# 1.net
KiCad netlist of a schematic drawn in Altium Designer
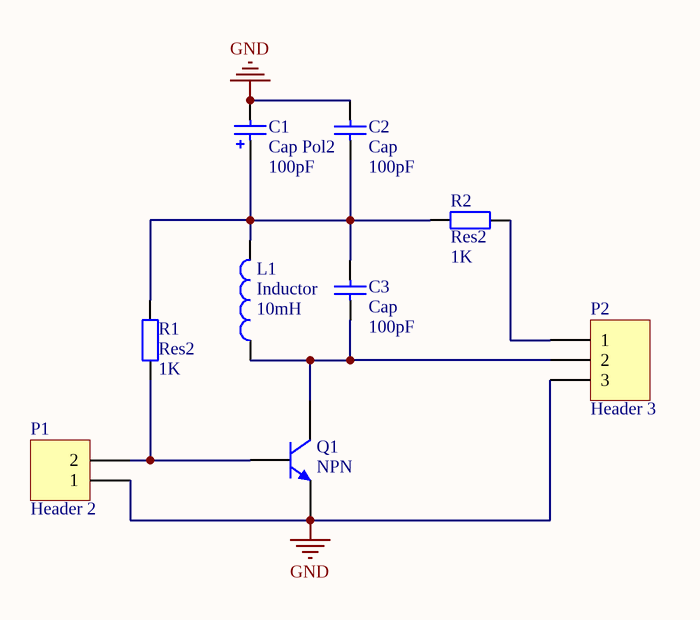
[diagram p0: 原理图1.SchDoc]

(export (version "E")
  (design (tool "Eeschema 10.0.6"))
  (components
    (comp (ref "C1")
      (value "Cap Pol2")
      (footprint "POLAR0.8")
      (description "Polarized Capacitor (Axial)")
      (fields (field (name "ALTIUM_VALUE") "100pF") (field (name "PUBLISHER") "Altium Limited"))
      (libsource (lib "Miscellaneous Devices") (part "Cap Pol2"))
    )
    (comp (ref "C2")
      (value "Cap")
      (footprint "RAD-0.3")
      (description "Capacitor")
      (fields (field (name "ALTIUM_VALUE") "100pF") (field (name "PUBLISHER") "Altium Limited"))
      (libsource (lib "Miscellaneous Devices") (part "Cap"))
    )
    (comp (ref "C3")
      (value "Cap")
      (footprint "RAD-0.3")
      (description "Capacitor")
      (fields (field (name "ALTIUM_VALUE") "100pF") (field (name "PUBLISHER") "Altium Limited"))
      (libsource (lib "Miscellaneous Devices") (part "Cap"))
    )
    (comp (ref "L1")
      (value "Inductor")
      (footprint "0402-A")
      (fields (field (name "ALTIUM_VALUE") "10mH") (field (name "PUBLISHER") "Altium Limited"))
      (libsource (lib "Miscellaneous Devices") (part "Inductor"))
    )
    (comp (ref "P1")
      (value "Header 2")
      (footprint "HDR1X2")
      (description "Header, 2-Pin")
      (fields (field (name "PUBLISHER") "Altium Limited"))
      (libsource (lib "Miscellaneous Connectors") (part "Header 2"))
    )
    (comp (ref "P2")
      (value "Header 3")
      (footprint "HDR1X3")
      (description "Header, 3-Pin")
      (fields (field (name "PUBLISHER") "Altium Limited"))
      (libsource (lib "Miscellaneous Connectors") (part "Header 3"))
    )
    (comp (ref "Q1")
      (value "NPN")
      (footprint "TO-226-AA")
      (description "NPN Bipolar Transistor")
      (fields (field (name "PUBLISHER") "Altium Limited"))
      (libsource (lib "Miscellaneous Devices") (part "NPN"))
    )
    (comp (ref "R1")
      (value "Res2")
      (footprint "AXIAL-0.4")
      (description "Resistor")
      (fields (field (name "ALTIUM_VALUE") "1K") (field (name "PUBLISHER") "Altium Limited"))
      (libsource (lib "") (part "Res2_1"))
    )
    (comp (ref "R2")
      (value "Res2")
      (footprint "AXIAL-0.4")
      (description "Resistor")
      (fields (field (name "ALTIUM_VALUE") "1K") (field (name "PUBLISHER") "Altium Limited"))
      (libsource (lib "Miscellaneous Devices") (part "Res2"))
    )
  )
  (nets
    (net (code "1") (name "GND") (class "Default")
      (node (ref "C1") (pin "2") (pinfunction "2_2") (pintype "passive"))
      (node (ref "C2") (pin "2") (pinfunction "2_2") (pintype "passive"))
      (node (ref "P1") (pin "1") (pinfunction "1_1") (pintype "passive"))
      (node (ref "P2") (pin "3") (pinfunction "3_3") (pintype "passive"))
      (node (ref "Q1") (pin "3") (pinfunction "E_3") (pintype "passive"))
    )
    (net (code "2") (name "Net-(C1-Pad1)") (class "Default")
      (node (ref "C1") (pin "1") (pinfunction "1_1") (pintype "passive"))
      (node (ref "C2") (pin "1") (pinfunction "1_1") (pintype "passive"))
      (node (ref "C3") (pin "2") (pinfunction "2_2") (pintype "passive"))
      (node (ref "L1") (pin "2") (pinfunction "2_2") (pintype "passive"))
      (node (ref "R1") (pin "2") (pinfunction "2_2") (pintype "passive"))
      (node (ref "R2") (pin "2") (pinfunction "2_2") (pintype "passive"))
    )
    (net (code "3") (name "Net-(P2-Pad1)") (class "Default")
      (node (ref "P2") (pin "1") (pinfunction "1_1") (pintype "passive"))
      (node (ref "R2") (pin "1") (pinfunction "1_1") (pintype "passive"))
    )
    (net (code "4") (name "Net-(Q1-B)") (class "Default")
      (node (ref "P1") (pin "2") (pinfunction "2_2") (pintype "passive"))
      (node (ref "Q1") (pin "2") (pinfunction "B_2") (pintype "passive"))
      (node (ref "R1") (pin "1") (pinfunction "1_1") (pintype "passive"))
    )
    (net (code "5") (name "Net-(Q1-C)") (class "Default")
      (node (ref "C3") (pin "1") (pinfunction "1_1") (pintype "passive"))
      (node (ref "L1") (pin "1") (pinfunction "1_1") (pintype "passive"))
      (node (ref "P2") (pin "2") (pinfunction "2_2") (pintype "passive"))
      (node (ref "Q1") (pin "1") (pinfunction "C_1") (pintype "passive"))
    )
  )
)
